# Barrido2fuentes.net
KiCad netlist of a schematic drawn in Altium Designer
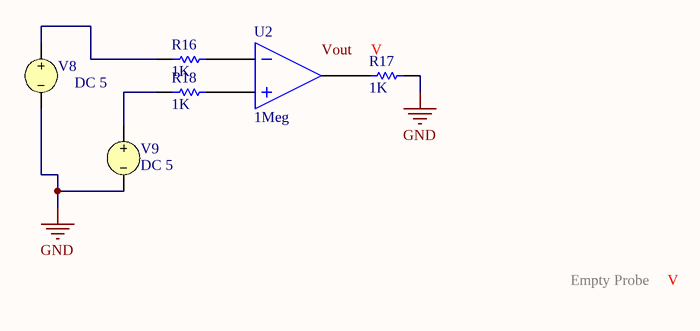
[diagram p0: Barrido2fuentes.SchDoc]

(export (version "E")
  (design (tool "Eeschema 10.0.6"))
  (components
    (comp (ref "R16")
      (value "1K")
      (description "Resistor")
      (libsource (lib "Simulation Generic Components") (part "Resistor"))
    )
    (comp (ref "R17")
      (value "1K")
      (description "Resistor")
      (libsource (lib "Simulation Generic Components") (part "Resistor"))
    )
    (comp (ref "R18")
      (value "1K")
      (description "Resistor")
      (libsource (lib "Simulation Generic Components") (part "Resistor"))
    )
    (comp (ref "U2")
      (value "Ideal Operational Amplifier")
      (fields (field (name "GAIN") "1Meg"))
      (libsource (lib "Simulation Generic Components") (part "OpAmp"))
    )
    (comp (ref "V8")
      (value "DC 5")
      (description "Voltage Source")
      (fields (field (name "PUBLISHER") "Altium Limited"))
      (libsource (lib "Simulation Generic Components") (part "VSRC"))
    )
    (comp (ref "V9")
      (value "DC 5")
      (description "Voltage Source")
      (fields (field (name "PUBLISHER") "Altium Limited"))
      (libsource (lib "Simulation Generic Components") (part "VSRC"))
    )
  )
  (nets
    (net (code "2") (name "GND") (class "Default")
      (node (ref "R17") (pin "2") (pinfunction "2_2") (pintype "passive"))
      (node (ref "V8") (pin "2") (pinfunction "2_2") (pintype "passive"))
      (node (ref "V9") (pin "2") (pinfunction "2_2") (pintype "passive"))
    )
    (net (code "3") (name "Net-(R16-Pad1)") (class "Default")
      (node (ref "R16") (pin "1") (pinfunction "1_1") (pintype "passive"))
      (node (ref "V8") (pin "1") (pinfunction "1_1") (pintype "passive"))
    )
    (net (code "4") (name "Net-(R18-Pad1)") (class "Default")
      (node (ref "R18") (pin "1") (pinfunction "1_1") (pintype "passive"))
      (node (ref "V9") (pin "1") (pinfunction "1_1") (pintype "passive"))
    )
    (net (code "5") (name "Net-(U2-IN+)") (class "Default")
      (node (ref "R18") (pin "2") (pinfunction "2_2") (pintype "passive"))
      (node (ref "U2") (pin "2") (pinfunction "IN+_2") (pintype "passive"))
    )
    (net (code "6") (name "Net-(U2-IN-)") (class "Default")
      (node (ref "R16") (pin "2") (pinfunction "2_2") (pintype "passive"))
      (node (ref "U2") (pin "1") (pinfunction "IN-_1") (pintype "passive"))
    )
    (net (code "7") (name "Net-(U2-OUT)") (class "Default")
      (node (ref "R17") (pin "1") (pinfunction "1_1") (pintype "passive"))
      (node (ref "U2") (pin "3") (pinfunction "OUT_3") (pintype "passive"))
    )
  )
)
